# sot23-5_6.net
KiCad netlist of a schematic drawn in EAGLE
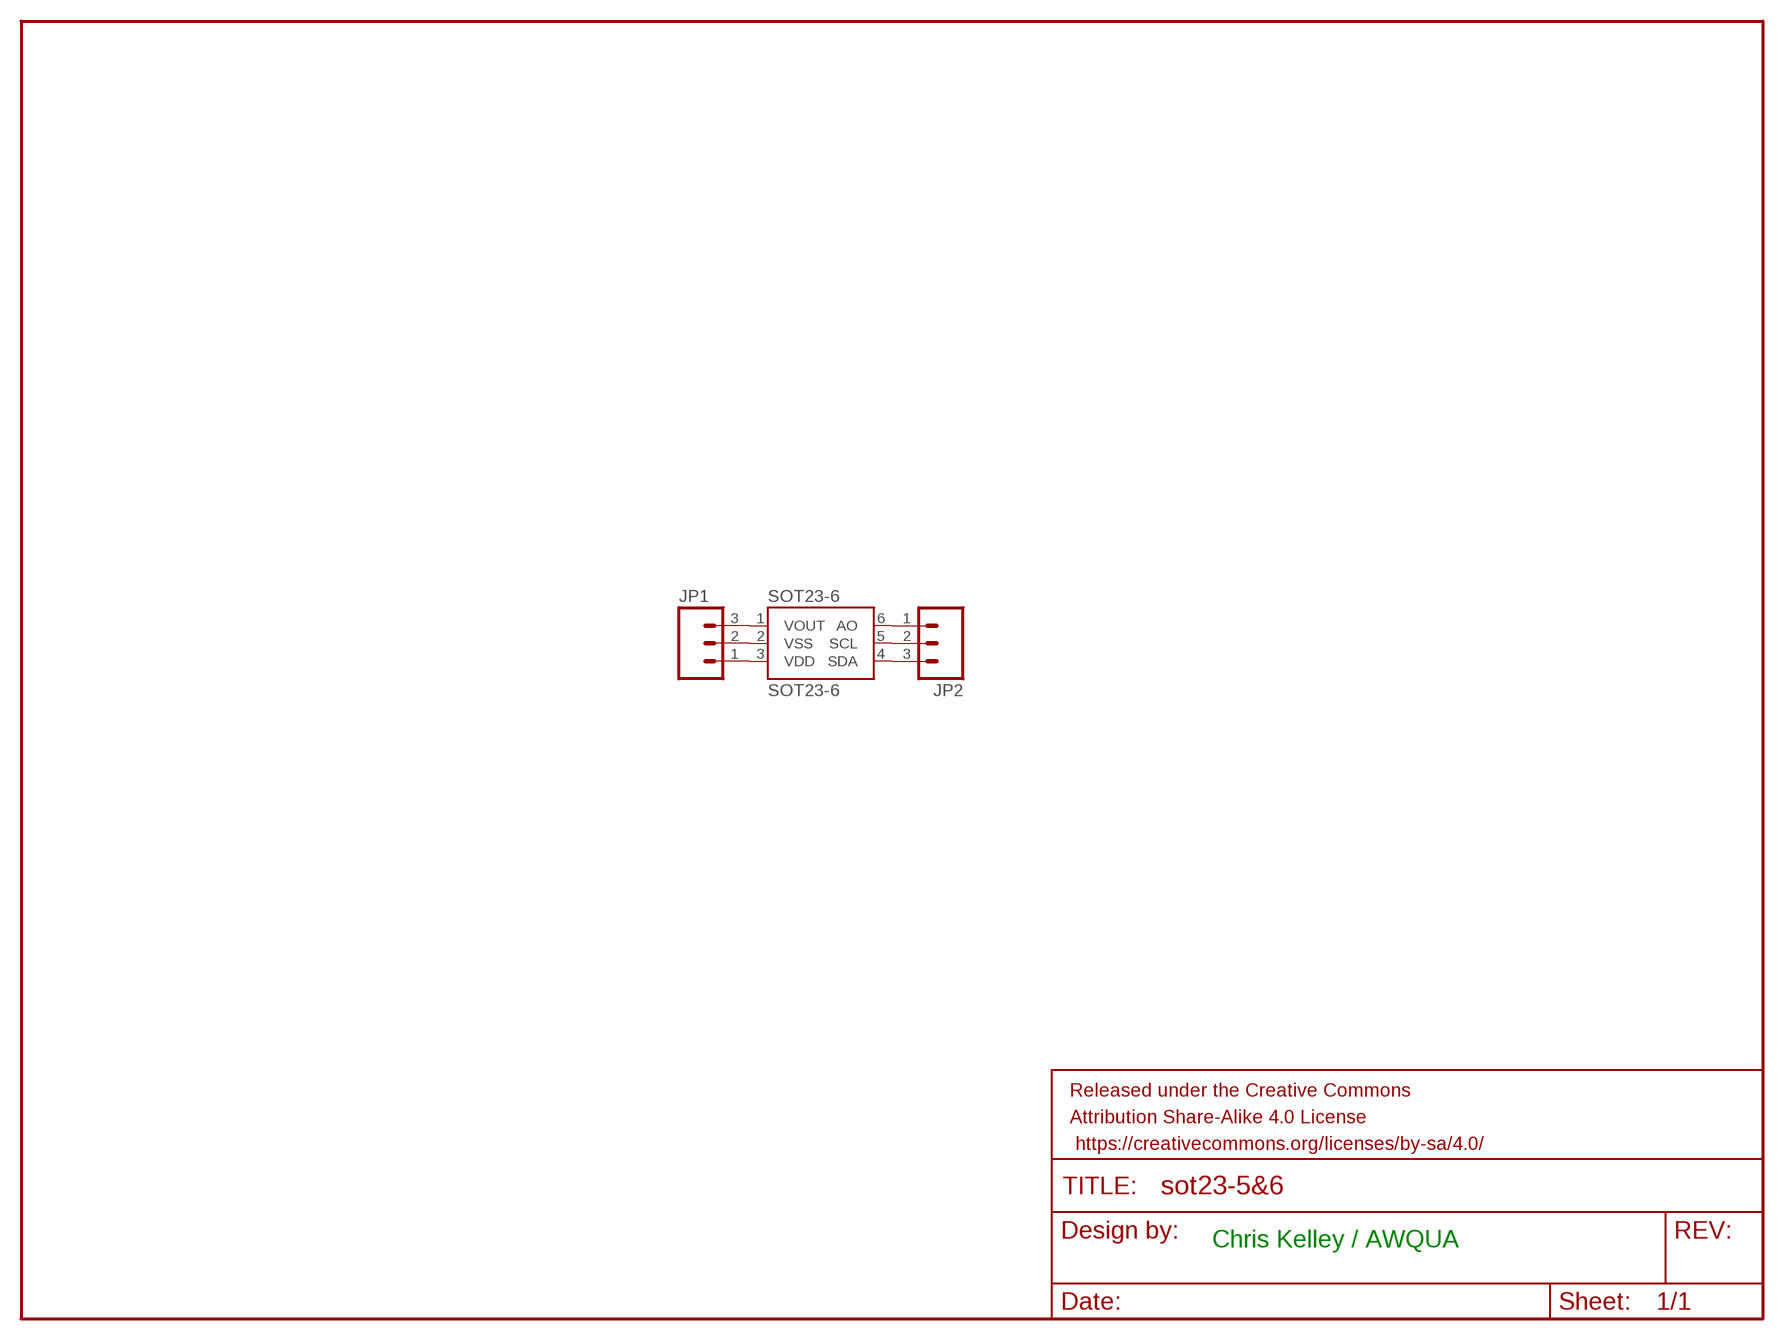
[diagram p0: schematic, sheet 1]

(export (version "E")
  (design (tool "Eeschema 10.0.6"))
  (components
    (comp (ref "FRAME1")
      (value "FRAME-LETTER")
      (footprint "eagle-import:CREATIVE_COMMONS")
      (libsource (lib "eagle-import") (part "FRAME-LETTER"))
    )
    (comp (ref "JP1")
      (value "M03PTH")
      (footprint "eagle-import:1X03")
      (libsource (lib "eagle-import") (part "M03PTH"))
    )
    (comp (ref "JP2")
      (value "M03PTH")
      (footprint "eagle-import:1X03")
      (libsource (lib "eagle-import") (part "M03PTH"))
    )
    (comp (ref "SOT23-6")
      (value "SOT23-6")
      (footprint "eagle-import:SOT23-6")
      (libsource (lib "eagle-import") (part "MCP4725SOT-23"))
    )
  )
  (nets
    (net (code "1") (name "Net-(SOT23-6-AO)") (class "Default")
      (node (ref "JP2") (pin "1") (pinfunction "1_1") (pintype "passive"))
      (node (ref "SOT23-6") (pin "6") (pinfunction "AO_6") (pintype "bidirectional"))
    )
    (net (code "2") (name "Net-(SOT23-6-SCL)") (class "Default")
      (node (ref "JP2") (pin "2") (pinfunction "2_2") (pintype "passive"))
      (node (ref "SOT23-6") (pin "5") (pinfunction "SCL_5") (pintype "bidirectional"))
    )
    (net (code "3") (name "Net-(SOT23-6-SDA)") (class "Default")
      (node (ref "JP2") (pin "3") (pinfunction "3_3") (pintype "passive"))
      (node (ref "SOT23-6") (pin "4") (pinfunction "SDA_4") (pintype "bidirectional"))
    )
    (net (code "4") (name "Net-(SOT23-6-VDD)") (class "Default")
      (node (ref "JP1") (pin "1") (pinfunction "1_1") (pintype "passive"))
      (node (ref "SOT23-6") (pin "3") (pinfunction "VDD_3") (pintype "bidirectional"))
    )
    (net (code "5") (name "Net-(SOT23-6-VOUT)") (class "Default")
      (node (ref "JP1") (pin "3") (pinfunction "3_3") (pintype "passive"))
      (node (ref "SOT23-6") (pin "1") (pinfunction "VOUT_1") (pintype "bidirectional"))
    )
    (net (code "6") (name "Net-(SOT23-6-VSS)") (class "Default")
      (node (ref "JP1") (pin "2") (pinfunction "2_2") (pintype "passive"))
      (node (ref "SOT23-6") (pin "2") (pinfunction "VSS_2") (pintype "bidirectional"))
    )
  )
)
